# EMG_CHANNEL_1_ANALOG.net
KiCad netlist of a schematic drawn in Altium Designer
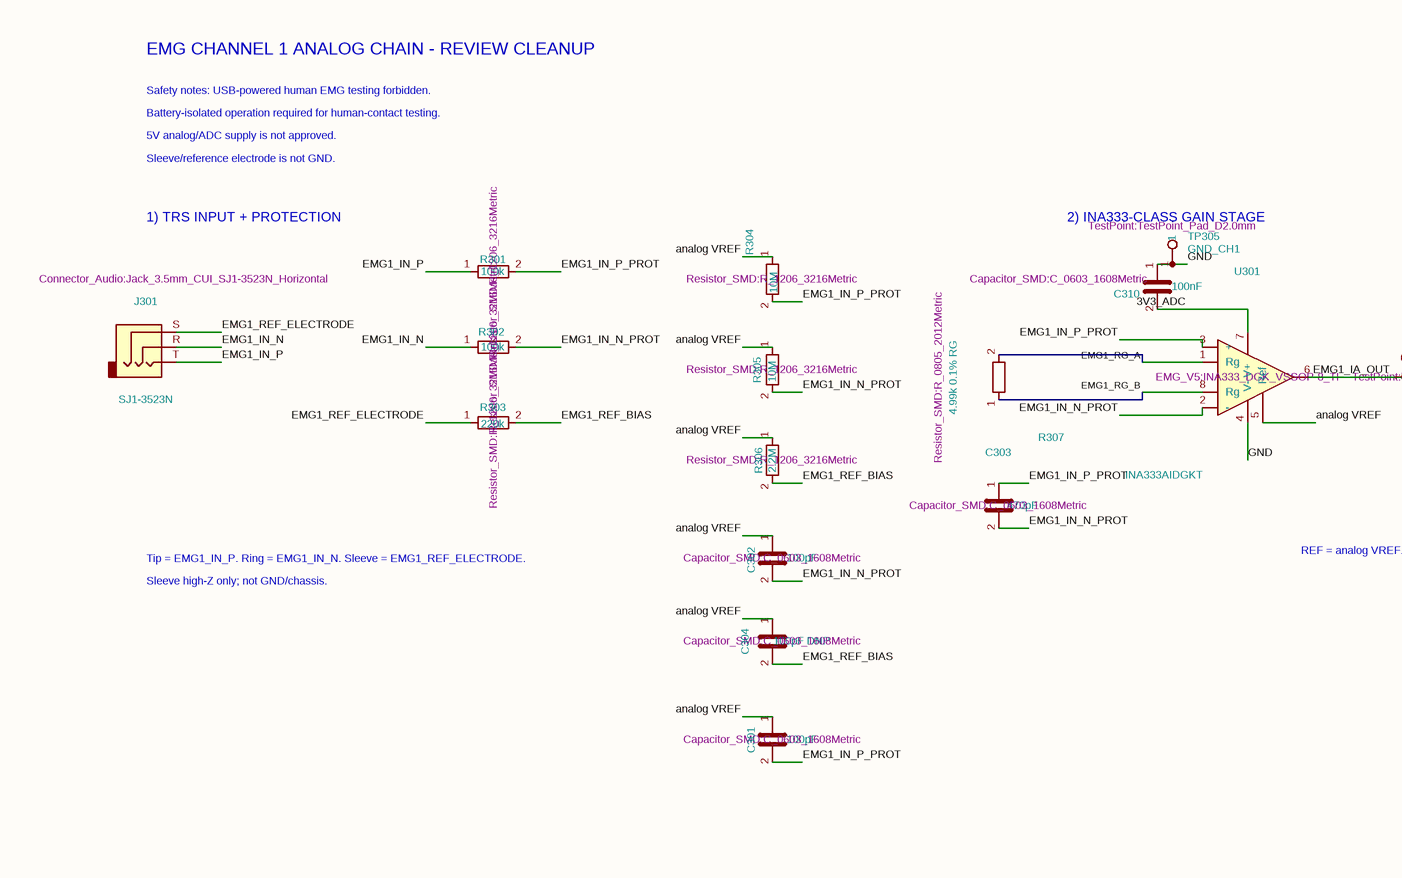
[diagram p0: EMG_CHANNEL_1_ANALOG.SchDoc, left]
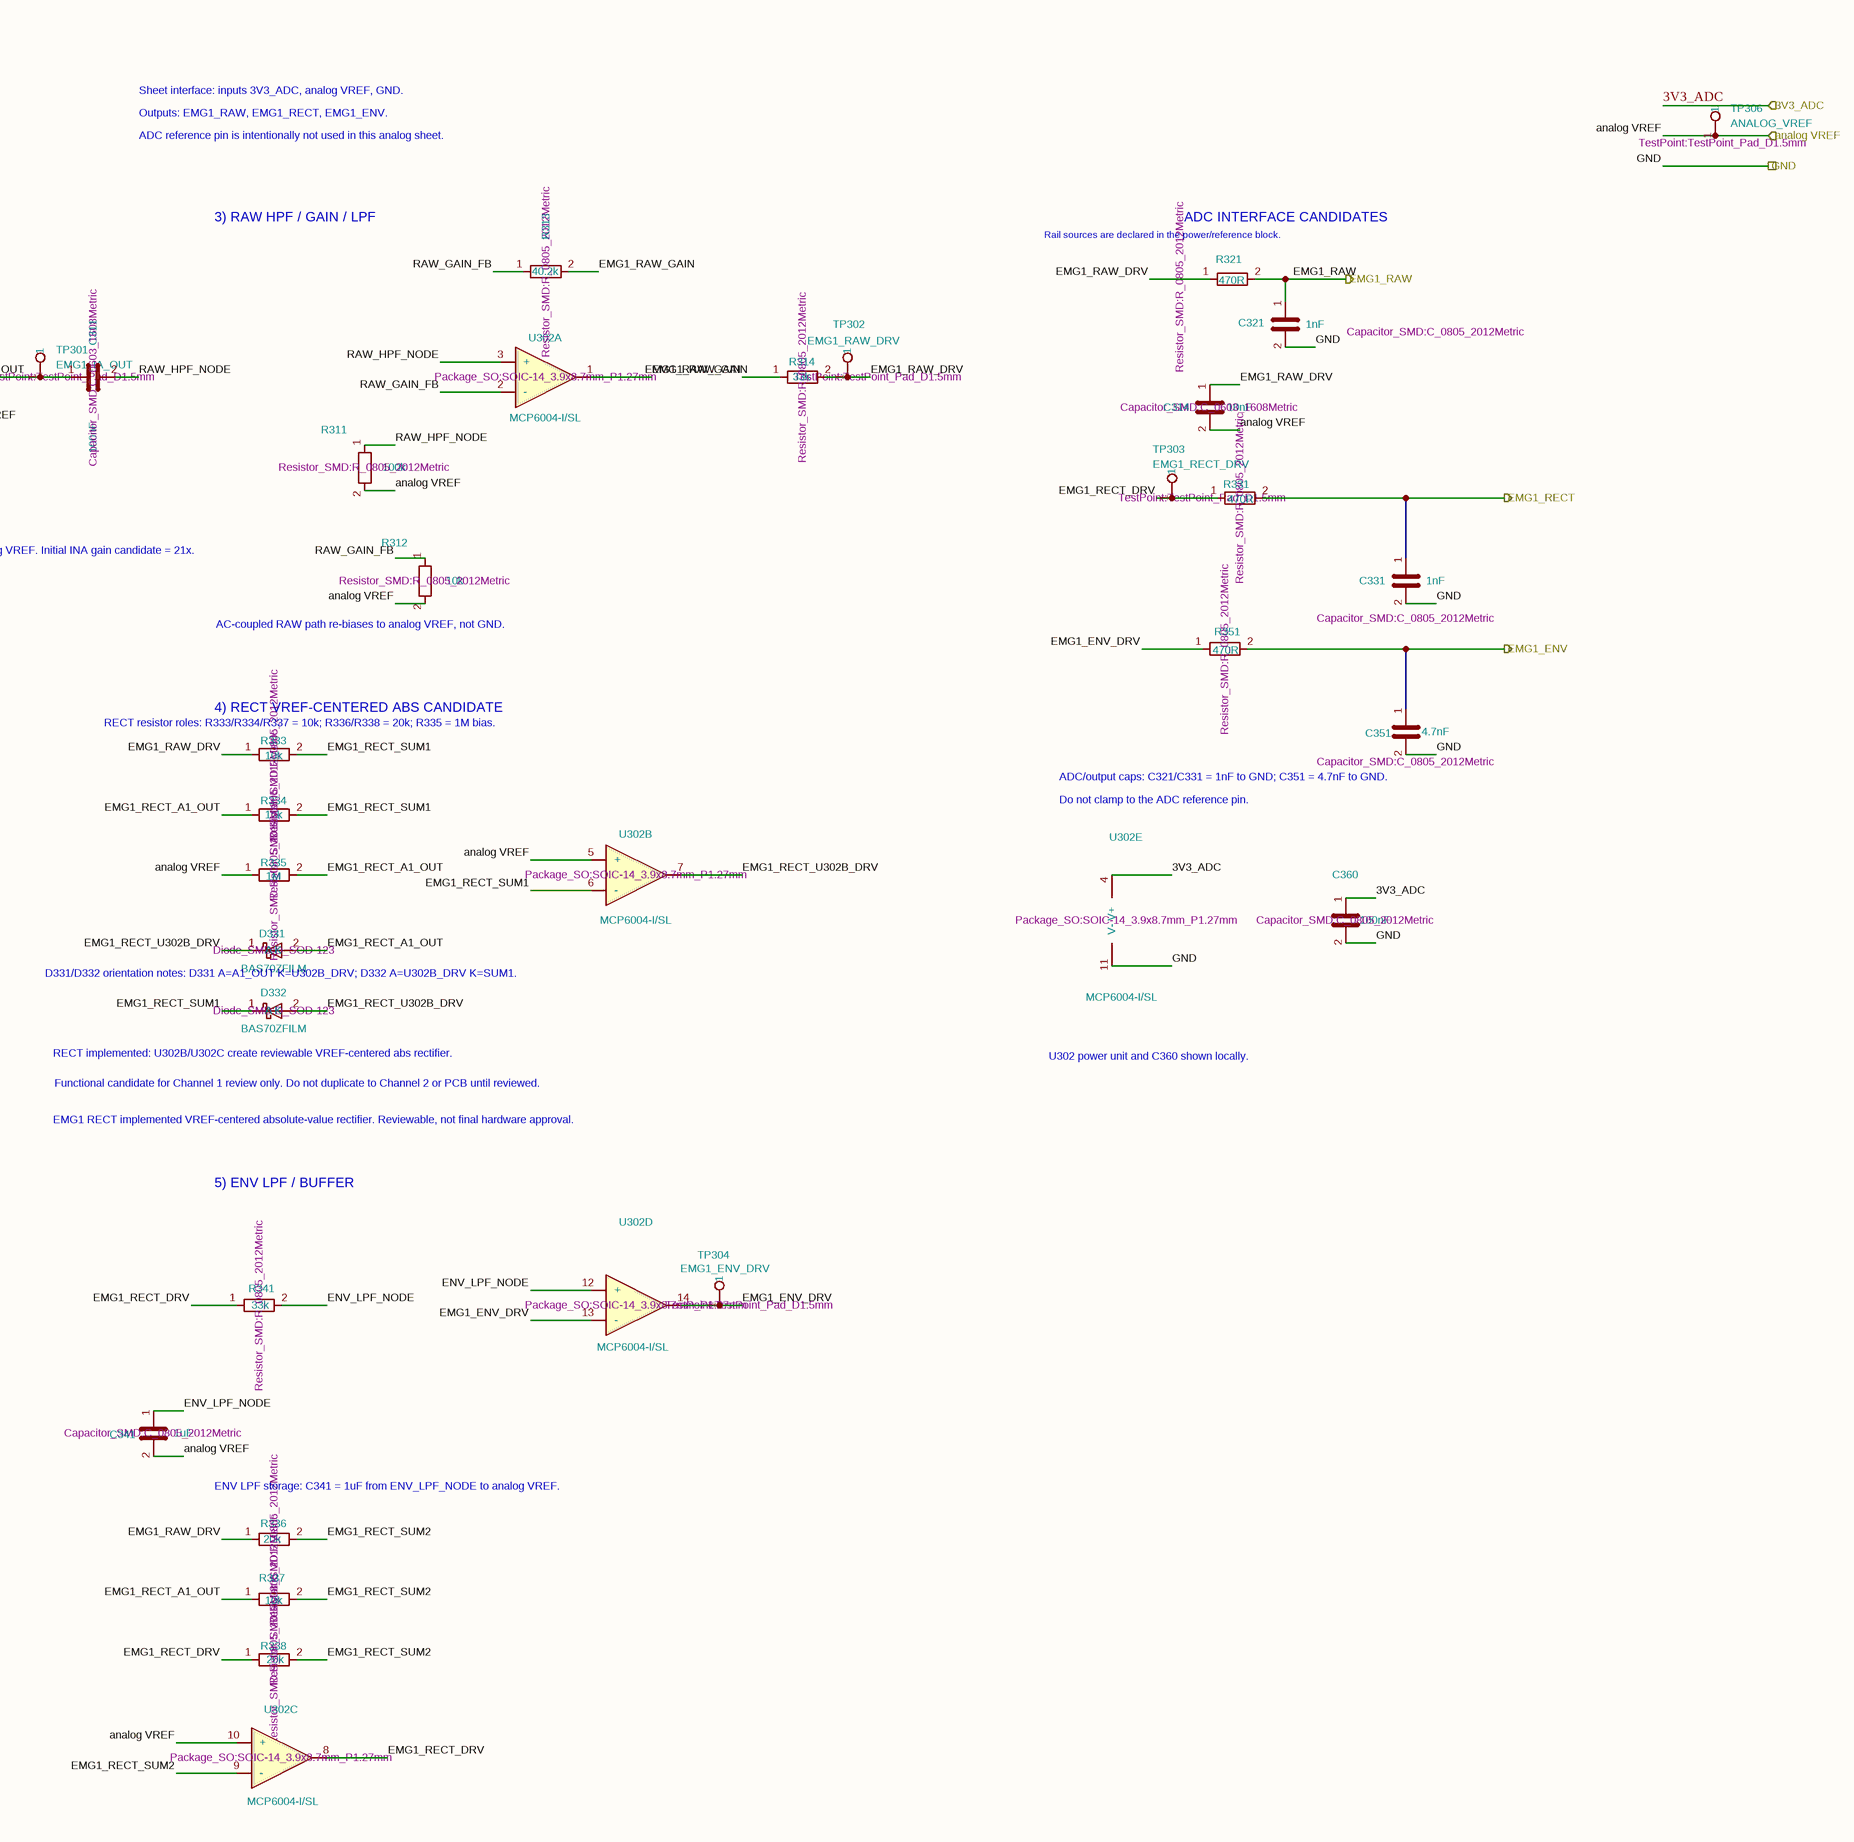
[diagram p1: EMG_CHANNEL_1_ANALOG.SchDoc, right]

(export (version "E")
  (design (tool "Eeschema 10.0.6"))
  (components
    (comp (ref "C301")
      (value "100pF")
      (footprint "Capacitor_SMD:C_0603_1608Metric")
      (libsource (lib "Device") (part "C"))
    )
    (comp (ref "C302")
      (value "100pF")
      (footprint "Capacitor_SMD:C_0603_1608Metric")
      (libsource (lib "Device") (part "C"))
    )
    (comp (ref "C303")
      (value "470pF")
      (footprint "Capacitor_SMD:C_0603_1608Metric")
      (libsource (lib "Device") (part "C"))
    )
    (comp (ref "C304")
      (value "100pF DNP")
      (footprint "Capacitor_SMD:C_0603_1608Metric")
      (libsource (lib "Device") (part "C"))
    )
    (comp (ref "C310")
      (value "100nF")
      (footprint "Capacitor_SMD:C_0603_1608Metric")
      (libsource (lib "Device") (part "C"))
    )
    (comp (ref "C311")
      (value "100nF")
      (footprint "Capacitor_SMD:C_0603_1608Metric")
      (libsource (lib "Device") (part "C"))
    )
    (comp (ref "C314")
      (value "10nF")
      (footprint "Capacitor_SMD:C_0603_1608Metric")
      (libsource (lib "Device") (part "C"))
    )
    (comp (ref "C321")
      (value "1nF")
      (footprint "Capacitor_SMD:C_0805_2012Metric")
      (libsource (lib "Device") (part "C"))
    )
    (comp (ref "C331")
      (value "1nF")
      (footprint "Capacitor_SMD:C_0805_2012Metric")
      (libsource (lib "Device") (part "C"))
    )
    (comp (ref "C341")
      (value "1uF")
      (footprint "Capacitor_SMD:C_0805_2012Metric")
      (libsource (lib "Device") (part "C"))
    )
    (comp (ref "C351")
      (value "4.7nF")
      (footprint "Capacitor_SMD:C_0805_2012Metric")
      (libsource (lib "Device") (part "C"))
    )
    (comp (ref "C360")
      (value "100nF")
      (footprint "Capacitor_SMD:C_0805_2012Metric")
      (libsource (lib "Device") (part "C"))
    )
    (comp (ref "D331")
      (value "BAS70ZFILM")
      (footprint "Diode_SMD:D_SOD-123")
      (libsource (lib "Device") (part "D_Schottky"))
    )
    (comp (ref "D332")
      (value "BAS70ZFILM")
      (footprint "Diode_SMD:D_SOD-123")
      (libsource (lib "Device") (part "D_Schottky"))
    )
    (comp (ref "J301")
      (value "SJ1-3523N")
      (footprint "Connector_Audio:Jack_3.5mm_CUI_SJ1-3523N_Horizontal")
      (libsource (lib "Connector_Audio") (part "AudioJack3"))
    )
    (comp (ref "R301")
      (value "100k")
      (footprint "Resistor_SMD:R_1206_3216Metric")
      (libsource (lib "") (part "R_1"))
    )
    (comp (ref "R302")
      (value "100k")
      (footprint "Resistor_SMD:R_1206_3216Metric")
      (libsource (lib "") (part "R_1"))
    )
    (comp (ref "R303")
      (value "220k")
      (footprint "Resistor_SMD:R_1206_3216Metric")
      (libsource (lib "") (part "R_1"))
    )
    (comp (ref "R304")
      (value "10M")
      (footprint "Resistor_SMD:R_1206_3216Metric")
      (libsource (lib "Device") (part "R"))
    )
    (comp (ref "R305")
      (value "10M")
      (footprint "Resistor_SMD:R_1206_3216Metric")
      (libsource (lib "Device") (part "R"))
    )
    (comp (ref "R306")
      (value "2.2M")
      (footprint "Resistor_SMD:R_1206_3216Metric")
      (libsource (lib "Device") (part "R"))
    )
    (comp (ref "R307")
      (value "4.99k 0.1% RG")
      (footprint "Resistor_SMD:R_0805_2012Metric")
      (libsource (lib "") (part "R_2"))
    )
    (comp (ref "R311")
      (value "100k")
      (footprint "Resistor_SMD:R_0805_2012Metric")
      (libsource (lib "Device") (part "R"))
    )
    (comp (ref "R312")
      (value "10k")
      (footprint "Resistor_SMD:R_0805_2012Metric")
      (libsource (lib "Device") (part "R"))
    )
    (comp (ref "R313")
      (value "40.2k")
      (footprint "Resistor_SMD:R_0805_2012Metric")
      (libsource (lib "") (part "R_1"))
    )
    (comp (ref "R314")
      (value "33k")
      (footprint "Resistor_SMD:R_0805_2012Metric")
      (libsource (lib "") (part "R_1"))
    )
    (comp (ref "R321")
      (value "470R")
      (footprint "Resistor_SMD:R_0805_2012Metric")
      (libsource (lib "") (part "R_1"))
    )
    (comp (ref "R331")
      (value "470R")
      (footprint "Resistor_SMD:R_0805_2012Metric")
      (libsource (lib "") (part "R_1"))
    )
    (comp (ref "R333")
      (value "10k")
      (footprint "Resistor_SMD:R_0805_2012Metric")
      (libsource (lib "") (part "R_1"))
    )
    (comp (ref "R334")
      (value "10k")
      (footprint "Resistor_SMD:R_0805_2012Metric")
      (libsource (lib "") (part "R_1"))
    )
    (comp (ref "R335")
      (value "1M")
      (footprint "Resistor_SMD:R_0805_2012Metric")
      (libsource (lib "") (part "R_1"))
    )
    (comp (ref "R336")
      (value "20k")
      (footprint "Resistor_SMD:R_0805_2012Metric")
      (libsource (lib "") (part "R_1"))
    )
    (comp (ref "R337")
      (value "10k")
      (footprint "Resistor_SMD:R_0805_2012Metric")
      (libsource (lib "") (part "R_1"))
    )
    (comp (ref "R338")
      (value "20k")
      (footprint "Resistor_SMD:R_0805_2012Metric")
      (libsource (lib "") (part "R_1"))
    )
    (comp (ref "R341")
      (value "33k")
      (footprint "Resistor_SMD:R_0805_2012Metric")
      (libsource (lib "") (part "R_1"))
    )
    (comp (ref "R351")
      (value "470R")
      (footprint "Resistor_SMD:R_0805_2012Metric")
      (libsource (lib "") (part "R_1"))
    )
    (comp (ref "TP301")
      (value "EMG1_IA_OUT")
      (footprint "TestPoint:TestPoint_Pad_D1.5mm")
      (libsource (lib "Connector") (part "TestPoint"))
    )
    (comp (ref "TP302")
      (value "EMG1_RAW_DRV")
      (footprint "TestPoint:TestPoint_Pad_D1.5mm")
      (libsource (lib "Connector") (part "TestPoint"))
    )
    (comp (ref "TP303")
      (value "EMG1_RECT_DRV")
      (footprint "TestPoint:TestPoint_Pad_D1.5mm")
      (libsource (lib "Connector") (part "TestPoint"))
    )
    (comp (ref "TP304")
      (value "EMG1_ENV_DRV")
      (footprint "TestPoint:TestPoint_Pad_D1.5mm")
      (libsource (lib "Connector") (part "TestPoint"))
    )
    (comp (ref "TP305")
      (value "GND_CH1")
      (footprint "TestPoint:TestPoint_Pad_D2.0mm")
      (libsource (lib "Connector") (part "TestPoint"))
    )
    (comp (ref "TP306")
      (value "ANALOG_VREF")
      (footprint "TestPoint:TestPoint_Pad_D1.5mm")
      (libsource (lib "Connector") (part "TestPoint"))
    )
    (comp (ref "U301")
      (value "INA333AIDGKT")
      (footprint "EMG_V5:INA333_DGK_VSSOP-8_TI")
      (libsource (lib "Amplifier_Instrumentation") (part "INA333xxDGK"))
    )
    (comp (ref "U302")
      (value "MCP6004-I/SL")
      (footprint "Package_SO:SOIC-14_3.9x8.7mm_P1.27mm")
      (libsource (lib "Amplifier_Operational") (part "MCP6004"))
    )
  )
  (nets
    (net (code "1") (name "/3V3_ADC") (class "Default")
      (node (ref "C310") (pin "2") (pinfunction "2_2") (pintype "passive"))
      (node (ref "C360") (pin "1") (pinfunction "1_1") (pintype "passive"))
      (node (ref "U301") (pin "7") (pinfunction "V+_7") (pintype "passive"))
      (node (ref "U302") (pin "4") (pinfunction "V+_4") (pintype "passive"))
    )
    (net (code "2") (name "/EMG1_ENV") (class "Default")
      (node (ref "C351") (pin "1") (pinfunction "1_1") (pintype "passive"))
      (node (ref "R351") (pin "2") (pinfunction "2_2") (pintype "passive"))
    )
    (net (code "3") (name "/EMG1_ENV_DRV") (class "Default")
      (node (ref "R351") (pin "1") (pinfunction "1_1") (pintype "passive"))
      (node (ref "TP304") (pin "1") (pinfunction "1_1") (pintype "passive"))
      (node (ref "U302") (pin "13") (pinfunction "-_13") (pintype "passive"))
      (node (ref "U302") (pin "14") (pinfunction "14_14") (pintype "passive"))
    )
    (net (code "4") (name "/EMG1_IA_OUT") (class "Default")
      (node (ref "C311") (pin "1") (pinfunction "1_1") (pintype "passive"))
      (node (ref "TP301") (pin "1") (pinfunction "1_1") (pintype "passive"))
      (node (ref "U301") (pin "6") (pinfunction "6_6") (pintype "passive"))
    )
    (net (code "5") (name "/EMG1_IN_N") (class "Default")
      (node (ref "J301") (pin "R") (pinfunction "R_R") (pintype "passive"))
      (node (ref "R302") (pin "1") (pinfunction "1_1") (pintype "passive"))
    )
    (net (code "6") (name "/EMG1_IN_N_PROT") (class "Default")
      (node (ref "C302") (pin "2") (pinfunction "2_2") (pintype "passive"))
      (node (ref "C303") (pin "2") (pinfunction "2_2") (pintype "passive"))
      (node (ref "R302") (pin "2") (pinfunction "2_2") (pintype "passive"))
      (node (ref "R305") (pin "2") (pinfunction "2_2") (pintype "passive"))
      (node (ref "U301") (pin "2") (pinfunction "-_2") (pintype "passive"))
    )
    (net (code "7") (name "/EMG1_IN_P") (class "Default")
      (node (ref "J301") (pin "T") (pinfunction "T_T") (pintype "passive"))
      (node (ref "R301") (pin "1") (pinfunction "1_1") (pintype "passive"))
    )
    (net (code "8") (name "/EMG1_IN_P_PROT") (class "Default")
      (node (ref "C301") (pin "2") (pinfunction "2_2") (pintype "passive"))
      (node (ref "C303") (pin "1") (pinfunction "1_1") (pintype "passive"))
      (node (ref "R301") (pin "2") (pinfunction "2_2") (pintype "passive"))
      (node (ref "R304") (pin "2") (pinfunction "2_2") (pintype "passive"))
      (node (ref "U301") (pin "3") (pinfunction "+_3") (pintype "passive"))
    )
    (net (code "9") (name "/EMG1_RAW") (class "Default")
      (node (ref "C321") (pin "1") (pinfunction "1_1") (pintype "passive"))
      (node (ref "R321") (pin "2") (pinfunction "2_2") (pintype "passive"))
    )
    (net (code "10") (name "/EMG1_RAW_DRV") (class "Default")
      (node (ref "C314") (pin "1") (pinfunction "1_1") (pintype "passive"))
      (node (ref "R314") (pin "2") (pinfunction "2_2") (pintype "passive"))
      (node (ref "R321") (pin "1") (pinfunction "1_1") (pintype "passive"))
      (node (ref "R333") (pin "1") (pinfunction "1_1") (pintype "passive"))
      (node (ref "R336") (pin "1") (pinfunction "1_1") (pintype "passive"))
      (node (ref "TP302") (pin "1") (pinfunction "1_1") (pintype "passive"))
    )
    (net (code "11") (name "/EMG1_RAW_GAIN") (class "Default")
      (node (ref "R313") (pin "2") (pinfunction "2_2") (pintype "passive"))
      (node (ref "R314") (pin "1") (pinfunction "1_1") (pintype "passive"))
      (node (ref "U302") (pin "1") (pinfunction "1_1") (pintype "passive"))
    )
    (net (code "12") (name "/EMG1_RECT") (class "Default")
      (node (ref "C331") (pin "1") (pinfunction "1_1") (pintype "passive"))
      (node (ref "R331") (pin "2") (pinfunction "2_2") (pintype "passive"))
    )
    (net (code "13") (name "/EMG1_RECT_A1_OUT") (class "Default")
      (node (ref "D331") (pin "2") (pinfunction "A_2") (pintype "passive"))
      (node (ref "R334") (pin "1") (pinfunction "1_1") (pintype "passive"))
      (node (ref "R335") (pin "2") (pinfunction "2_2") (pintype "passive"))
      (node (ref "R337") (pin "1") (pinfunction "1_1") (pintype "passive"))
    )
    (net (code "14") (name "/EMG1_RECT_DRV") (class "Default")
      (node (ref "R331") (pin "1") (pinfunction "1_1") (pintype "passive"))
      (node (ref "R338") (pin "1") (pinfunction "1_1") (pintype "passive"))
      (node (ref "R341") (pin "1") (pinfunction "1_1") (pintype "passive"))
      (node (ref "TP303") (pin "1") (pinfunction "1_1") (pintype "passive"))
      (node (ref "U302") (pin "8") (pinfunction "8_8") (pintype "passive"))
    )
    (net (code "15") (name "/EMG1_RECT_SUM1") (class "Default")
      (node (ref "D332") (pin "1") (pinfunction "K_1") (pintype "passive"))
      (node (ref "R333") (pin "2") (pinfunction "2_2") (pintype "passive"))
      (node (ref "R334") (pin "2") (pinfunction "2_2") (pintype "passive"))
      (node (ref "U302") (pin "6") (pinfunction "-_6") (pintype "passive"))
    )
    (net (code "16") (name "/EMG1_RECT_SUM2") (class "Default")
      (node (ref "R336") (pin "2") (pinfunction "2_2") (pintype "passive"))
      (node (ref "R337") (pin "2") (pinfunction "2_2") (pintype "passive"))
      (node (ref "R338") (pin "2") (pinfunction "2_2") (pintype "passive"))
      (node (ref "U302") (pin "9") (pinfunction "-_9") (pintype "passive"))
    )
    (net (code "17") (name "/EMG1_RECT_U302B_DRV") (class "Default")
      (node (ref "D331") (pin "1") (pinfunction "K_1") (pintype "passive"))
      (node (ref "D332") (pin "2") (pinfunction "A_2") (pintype "passive"))
      (node (ref "U302") (pin "7") (pinfunction "7_7") (pintype "passive"))
    )
    (net (code "18") (name "/EMG1_REF_BIAS") (class "Default")
      (node (ref "C304") (pin "2") (pinfunction "2_2") (pintype "passive"))
      (node (ref "R303") (pin "2") (pinfunction "2_2") (pintype "passive"))
      (node (ref "R306") (pin "2") (pinfunction "2_2") (pintype "passive"))
    )
    (net (code "19") (name "/EMG1_REF_ELECTRODE") (class "Default")
      (node (ref "J301") (pin "S") (pinfunction "S_S") (pintype "passive"))
      (node (ref "R303") (pin "1") (pinfunction "1_1") (pintype "passive"))
    )
    (net (code "20") (name "/EMG1_RG_A") (class "Default")
      (node (ref "R307") (pin "2") (pinfunction "2_2") (pintype "passive"))
      (node (ref "U301") (pin "1") (pinfunction "Rg_1") (pintype "passive"))
    )
    (net (code "21") (name "/EMG1_RG_B") (class "Default")
      (node (ref "R307") (pin "1") (pinfunction "1_1") (pintype "passive"))
      (node (ref "U301") (pin "8") (pinfunction "Rg_8") (pintype "passive"))
    )
    (net (code "22") (name "/ENV_LPF_NODE") (class "Default")
      (node (ref "C341") (pin "1") (pinfunction "1_1") (pintype "passive"))
      (node (ref "R341") (pin "2") (pinfunction "2_2") (pintype "passive"))
      (node (ref "U302") (pin "12") (pinfunction "+_12") (pintype "passive"))
    )
    (net (code "23") (name "/GND") (class "Default")
      (node (ref "C310") (pin "1") (pinfunction "1_1") (pintype "passive"))
      (node (ref "C321") (pin "2") (pinfunction "2_2") (pintype "passive"))
      (node (ref "C331") (pin "2") (pinfunction "2_2") (pintype "passive"))
      (node (ref "C351") (pin "2") (pinfunction "2_2") (pintype "passive"))
      (node (ref "C360") (pin "2") (pinfunction "2_2") (pintype "passive"))
      (node (ref "TP305") (pin "1") (pinfunction "1_1") (pintype "passive"))
      (node (ref "U301") (pin "4") (pinfunction "V-_4") (pintype "passive"))
      (node (ref "U302") (pin "11") (pinfunction "V-_11") (pintype "passive"))
    )
    (net (code "24") (name "/RAW_GAIN_FB") (class "Default")
      (node (ref "R312") (pin "1") (pinfunction "1_1") (pintype "passive"))
      (node (ref "R313") (pin "1") (pinfunction "1_1") (pintype "passive"))
      (node (ref "U302") (pin "2") (pinfunction "-_2") (pintype "passive"))
    )
    (net (code "25") (name "/RAW_HPF_NODE") (class "Default")
      (node (ref "C311") (pin "2") (pinfunction "2_2") (pintype "passive"))
      (node (ref "R311") (pin "1") (pinfunction "1_1") (pintype "passive"))
      (node (ref "U302") (pin "3") (pinfunction "+_3") (pintype "passive"))
    )
    (net (code "26") (name "/analog VREF") (class "Default")
      (node (ref "C301") (pin "1") (pinfunction "1_1") (pintype "passive"))
      (node (ref "C302") (pin "1") (pinfunction "1_1") (pintype "passive"))
      (node (ref "C304") (pin "1") (pinfunction "1_1") (pintype "passive"))
      (node (ref "C314") (pin "2") (pinfunction "2_2") (pintype "passive"))
      (node (ref "C341") (pin "2") (pinfunction "2_2") (pintype "passive"))
      (node (ref "R304") (pin "1") (pinfunction "1_1") (pintype "passive"))
      (node (ref "R305") (pin "1") (pinfunction "1_1") (pintype "passive"))
      (node (ref "R306") (pin "1") (pinfunction "1_1") (pintype "passive"))
      (node (ref "R311") (pin "2") (pinfunction "2_2") (pintype "passive"))
      (node (ref "R312") (pin "2") (pinfunction "2_2") (pintype "passive"))
      (node (ref "R335") (pin "1") (pinfunction "1_1") (pintype "passive"))
      (node (ref "TP306") (pin "1") (pinfunction "1_1") (pintype "passive"))
      (node (ref "U301") (pin "5") (pinfunction "Ref_5") (pintype "passive"))
      (node (ref "U302") (pin "10") (pinfunction "+_10") (pintype "passive"))
      (node (ref "U302") (pin "5") (pinfunction "+_5") (pintype "passive"))
    )
  )
)
